# BB_ISP_v0_1.net
KiCad netlist of a schematic drawn in EAGLE
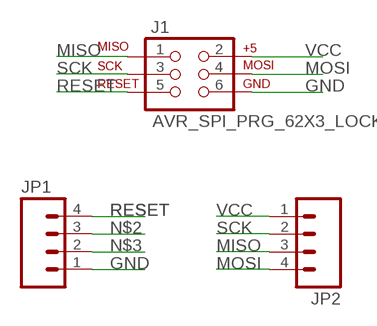
[diagram p0: schematic, sheet 1]

(export (version "E")
  (design (tool "Eeschema 10.0.6"))
  (components
    (comp (ref "J1")
      (value "AVR_SPI_PRG_62X3_LOCK")
      (footprint "eagle-import:2X3_LOCK")
      (libsource (lib "eagle-import") (part "AVR_SPI_PRG_62X3_LOCK"))
    )
    (comp (ref "JP1")
      (value "M04PTH")
      (footprint "eagle-import:1X04")
      (libsource (lib "eagle-import") (part "M04PTH"))
    )
    (comp (ref "JP2")
      (value "M04PTH")
      (footprint "eagle-import:1X04")
      (libsource (lib "eagle-import") (part "M04PTH"))
    )
  )
  (nets
    (net (code "1") (name "/GND") (class "Default")
      (node (ref "J1") (pin "6") (pinfunction "6_6") (pintype "passive"))
      (node (ref "JP1") (pin "1") (pinfunction "1_1") (pintype "passive"))
    )
    (net (code "2") (name "/MISO") (class "Default")
      (node (ref "J1") (pin "1") (pinfunction "1_1") (pintype "passive"))
      (node (ref "JP2") (pin "3") (pinfunction "3_3") (pintype "passive"))
    )
    (net (code "3") (name "/MOSI") (class "Default")
      (node (ref "J1") (pin "4") (pinfunction "4_4") (pintype "passive"))
      (node (ref "JP2") (pin "4") (pinfunction "4_4") (pintype "passive"))
    )
    (net (code "4") (name "/N$2") (class "Default")
      (node (ref "JP1") (pin "3") (pinfunction "3_3") (pintype "passive"))
    )
    (net (code "5") (name "/N$3") (class "Default")
      (node (ref "JP1") (pin "2") (pinfunction "2_2") (pintype "passive"))
    )
    (net (code "6") (name "/RESET") (class "Default")
      (node (ref "J1") (pin "5") (pinfunction "5_5") (pintype "passive"))
      (node (ref "JP1") (pin "4") (pinfunction "4_4") (pintype "passive"))
    )
    (net (code "7") (name "/SCK") (class "Default")
      (node (ref "J1") (pin "3") (pinfunction "3_3") (pintype "passive"))
      (node (ref "JP2") (pin "2") (pinfunction "2_2") (pintype "passive"))
    )
    (net (code "8") (name "/VCC") (class "Default")
      (node (ref "J1") (pin "2") (pinfunction "2_2") (pintype "passive"))
      (node (ref "JP2") (pin "1") (pinfunction "1_1") (pintype "passive"))
    )
  )
)
